# led_module.net
KiCad netlist of a schematic drawn in EAGLE
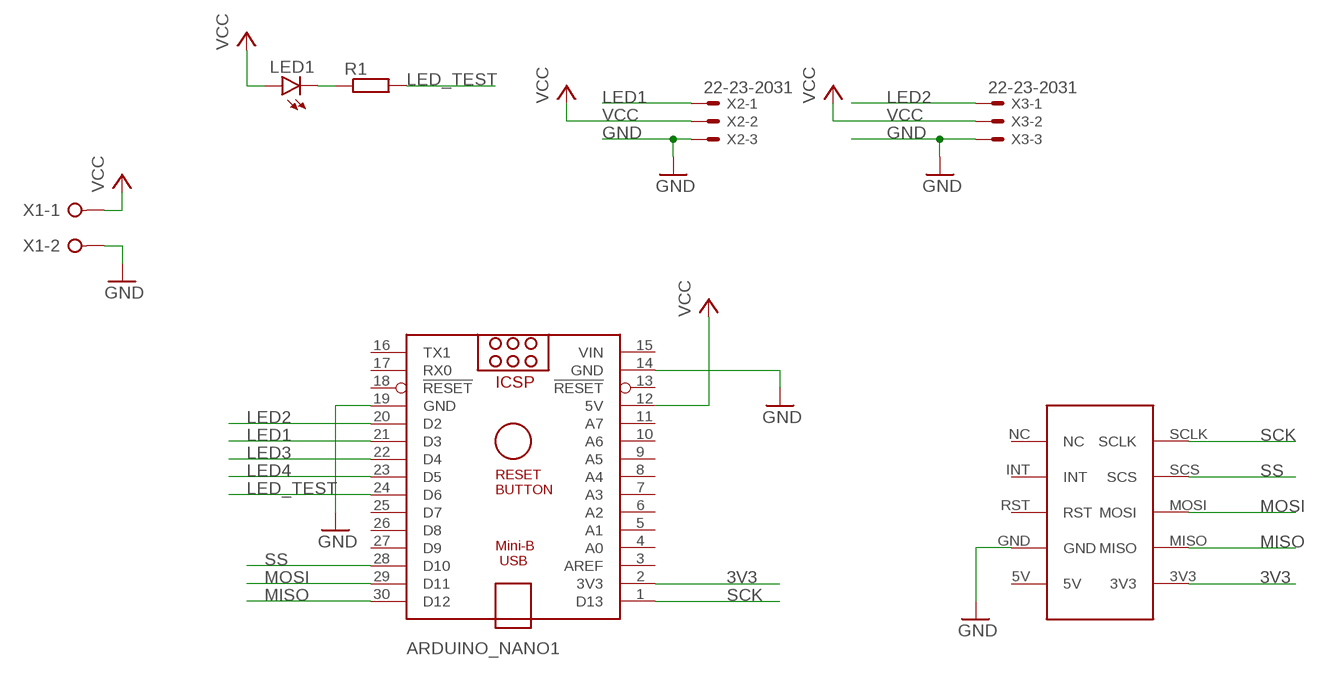
[diagram p0: schematic, sheet 1]

(export (version "E")
  (design (tool "Eeschema 10.0.6"))
  (components
    (comp (ref "ARDUINO_NANO1")
      (value "ARDUINO_NANO")
      (footprint "eagle-import:ARDUINO_NANO")
      (libsource (lib "eagle-import") (part "ARDUINO_NANO"))
    )
    (comp (ref "LED1")
      (value "LEDSML1206")
      (footprint "eagle-import:SML1206")
      (libsource (lib "eagle-import") (part "LEDSML1206"))
    )
    (comp (ref "R1")
      (value "R-EU_M1206")
      (footprint "eagle-import:M1206")
      (libsource (lib "eagle-import") (part "R-EU_M1206"))
    )
    (comp (ref "U$1")
      (value "W5500_MODULE")
      (footprint "eagle-import:W5500_MODULE")
      (libsource (lib "eagle-import") (part "W5500_MODULE"))
    )
    (comp (ref "X1")
      (value "W237-02P")
      (footprint "eagle-import:W237-132")
      (libsource (lib "eagle-import") (part "W237-02P"))
    )
    (comp (ref "X2")
      (value "22-23-2031")
      (footprint "eagle-import:22-23-2031")
      (fields (field (name "MF") "MOLEX"))
      (libsource (lib "eagle-import") (part "22-23-2031"))
    )
    (comp (ref "X3")
      (value "22-23-2031")
      (footprint "eagle-import:22-23-2031")
      (fields (field (name "MF") "MOLEX"))
      (libsource (lib "eagle-import") (part "22-23-2031"))
    )
  )
  (nets
    (net (code "1") (name "/3V3") (class "Default")
      (node (ref "ARDUINO_NANO1") (pin "2") (pinfunction "3V3_2") (pintype "output"))
      (node (ref "U$1") (pin "3V3") (pinfunction "3V3_3V3") (pintype "bidirectional"))
    )
    (net (code "2") (name "/LED1") (class "Default")
      (node (ref "ARDUINO_NANO1") (pin "21") (pinfunction "D3_21") (pintype "bidirectional"))
      (node (ref "X2") (pin "1") (pinfunction "S_1") (pintype "passive"))
    )
    (net (code "3") (name "/LED2") (class "Default")
      (node (ref "ARDUINO_NANO1") (pin "20") (pinfunction "D2_20") (pintype "bidirectional"))
      (node (ref "X3") (pin "1") (pinfunction "S_1") (pintype "passive"))
    )
    (net (code "4") (name "/LED3") (class "Default")
      (node (ref "ARDUINO_NANO1") (pin "22") (pinfunction "D4_22") (pintype "bidirectional"))
    )
    (net (code "5") (name "/LED4") (class "Default")
      (node (ref "ARDUINO_NANO1") (pin "23") (pinfunction "D5_23") (pintype "bidirectional"))
    )
    (net (code "6") (name "/LED_TEST") (class "Default")
      (node (ref "ARDUINO_NANO1") (pin "24") (pinfunction "D6_24") (pintype "bidirectional"))
      (node (ref "R1") (pin "2") (pinfunction "2_2") (pintype "passive"))
    )
    (net (code "7") (name "/MISO") (class "Default")
      (node (ref "ARDUINO_NANO1") (pin "30") (pinfunction "D12_30") (pintype "bidirectional"))
      (node (ref "U$1") (pin "MISO") (pinfunction "MISO_MISO") (pintype "bidirectional"))
    )
    (net (code "8") (name "/MOSI") (class "Default")
      (node (ref "ARDUINO_NANO1") (pin "29") (pinfunction "D11_29") (pintype "bidirectional"))
      (node (ref "U$1") (pin "MOSI") (pinfunction "MOSI_MOSI") (pintype "bidirectional"))
    )
    (net (code "9") (name "/SCK") (class "Default")
      (node (ref "ARDUINO_NANO1") (pin "1") (pinfunction "D13_1") (pintype "bidirectional"))
      (node (ref "U$1") (pin "SCLK") (pinfunction "SCLK_SCLK") (pintype "bidirectional"))
    )
    (net (code "10") (name "/SS") (class "Default")
      (node (ref "ARDUINO_NANO1") (pin "28") (pinfunction "D10_28") (pintype "bidirectional"))
      (node (ref "U$1") (pin "SCS") (pinfunction "SCS_SCS") (pintype "bidirectional"))
    )
    (net (code "11") (name "/VIN") (class "Default")
      (node (ref "ARDUINO_NANO1") (pin "15") (pinfunction "VIN_15") (pintype "power_in"))
    )
    (net (code "12") (name "GND") (class "Default")
      (node (ref "ARDUINO_NANO1") (pin "14") (pinfunction "GND_14") (pintype "power_in"))
      (node (ref "ARDUINO_NANO1") (pin "19") (pinfunction "GND_19") (pintype "power_in"))
      (node (ref "U$1") (pin "GND") (pinfunction "GND_GND") (pintype "bidirectional"))
      (node (ref "X1") (pin "2") (pinfunction "KL_2") (pintype "passive"))
      (node (ref "X2") (pin "3") (pinfunction "S_3") (pintype "passive"))
      (node (ref "X3") (pin "3") (pinfunction "S_3") (pintype "passive"))
    )
    (net (code "13") (name "Net-(LED1-PadC)") (class "Default")
      (node (ref "LED1") (pin "C") (pinfunction "C_C") (pintype "passive"))
      (node (ref "R1") (pin "1") (pinfunction "1_1") (pintype "passive"))
    )
    (net (code "14") (name "VCC") (class "Default")
      (node (ref "ARDUINO_NANO1") (pin "12") (pinfunction "5V_12") (pintype "power_in"))
      (node (ref "LED1") (pin "A") (pinfunction "A_A") (pintype "passive"))
      (node (ref "X1") (pin "1") (pinfunction "KL_1") (pintype "passive"))
      (node (ref "X2") (pin "2") (pinfunction "S_2") (pintype "passive"))
      (node (ref "X3") (pin "2") (pinfunction "S_2") (pintype "passive"))
    )
    (net (code "15") (name "unconnected-(ARDUINO_NANO1-A0-Pad4)") (class "Default")
      (node (ref "ARDUINO_NANO1") (pin "4") (pinfunction "A0_4") (pintype "bidirectional"))
    )
    (net (code "16") (name "unconnected-(ARDUINO_NANO1-A1-Pad5)") (class "Default")
      (node (ref "ARDUINO_NANO1") (pin "5") (pinfunction "A1_5") (pintype "bidirectional"))
    )
    (net (code "17") (name "unconnected-(ARDUINO_NANO1-A2-Pad6)") (class "Default")
      (node (ref "ARDUINO_NANO1") (pin "6") (pinfunction "A2_6") (pintype "bidirectional"))
    )
    (net (code "18") (name "unconnected-(ARDUINO_NANO1-A3-Pad7)") (class "Default")
      (node (ref "ARDUINO_NANO1") (pin "7") (pinfunction "A3_7") (pintype "bidirectional"))
    )
    (net (code "19") (name "unconnected-(ARDUINO_NANO1-A4-Pad8)") (class "Default")
      (node (ref "ARDUINO_NANO1") (pin "8") (pinfunction "A4_8") (pintype "bidirectional"))
    )
    (net (code "20") (name "unconnected-(ARDUINO_NANO1-A5-Pad9)") (class "Default")
      (node (ref "ARDUINO_NANO1") (pin "9") (pinfunction "A5_9") (pintype "bidirectional"))
    )
    (net (code "21") (name "unconnected-(ARDUINO_NANO1-A6-Pad10)") (class "Default")
      (node (ref "ARDUINO_NANO1") (pin "10") (pinfunction "A6_10") (pintype "bidirectional"))
    )
    (net (code "22") (name "unconnected-(ARDUINO_NANO1-A7-Pad11)") (class "Default")
      (node (ref "ARDUINO_NANO1") (pin "11") (pinfunction "A7_11") (pintype "bidirectional"))
    )
    (net (code "23") (name "unconnected-(ARDUINO_NANO1-AREF-Pad3)") (class "Default")
      (node (ref "ARDUINO_NANO1") (pin "3") (pinfunction "AREF_3") (pintype "input"))
    )
    (net (code "24") (name "unconnected-(ARDUINO_NANO1-D7-Pad25)") (class "Default")
      (node (ref "ARDUINO_NANO1") (pin "25") (pinfunction "D7_25") (pintype "bidirectional"))
    )
    (net (code "25") (name "unconnected-(ARDUINO_NANO1-D8-Pad26)") (class "Default")
      (node (ref "ARDUINO_NANO1") (pin "26") (pinfunction "D8_26") (pintype "bidirectional"))
    )
    (net (code "26") (name "unconnected-(ARDUINO_NANO1-D9-Pad27)") (class "Default")
      (node (ref "ARDUINO_NANO1") (pin "27") (pinfunction "D9_27") (pintype "bidirectional"))
    )
    (net (code "27") (name "unconnected-(ARDUINO_NANO1-RX0-Pad17)") (class "Default")
      (node (ref "ARDUINO_NANO1") (pin "17") (pinfunction "RX0_17") (pintype "bidirectional"))
    )
    (net (code "28") (name "unconnected-(ARDUINO_NANO1-TX1-Pad16)") (class "Default")
      (node (ref "ARDUINO_NANO1") (pin "16") (pinfunction "TX1_16") (pintype "bidirectional"))
    )
    (net (code "29") (name "unconnected-(ARDUINO_NANO1-~{RESET}-Pad13)") (class "Default")
      (node (ref "ARDUINO_NANO1") (pin "13") (pinfunction "~{RESET}_13") (pintype "input"))
    )
    (net (code "30") (name "unconnected-(ARDUINO_NANO1-~{RESET}-Pad18)") (class "Default")
      (node (ref "ARDUINO_NANO1") (pin "18") (pinfunction "~{RESET}_18") (pintype "input"))
    )
    (net (code "31") (name "unconnected-(U$1-Pad5V)") (class "Default")
      (node (ref "U$1") (pin "5V") (pinfunction "5V_5V") (pintype "bidirectional"))
    )
    (net (code "32") (name "unconnected-(U$1-PadINT)") (class "Default")
      (node (ref "U$1") (pin "INT") (pinfunction "INT_INT") (pintype "bidirectional"))
    )
    (net (code "33") (name "unconnected-(U$1-PadNC)") (class "Default")
      (node (ref "U$1") (pin "NC") (pinfunction "NC_NC") (pintype "bidirectional"))
    )
    (net (code "34") (name "unconnected-(U$1-PadRST)") (class "Default")
      (node (ref "U$1") (pin "RST") (pinfunction "RST_RST") (pintype "bidirectional"))
    )
  )
)
